# Serial_Load_Cell_converter.net
KiCad netlist of a schematic drawn in EAGLE
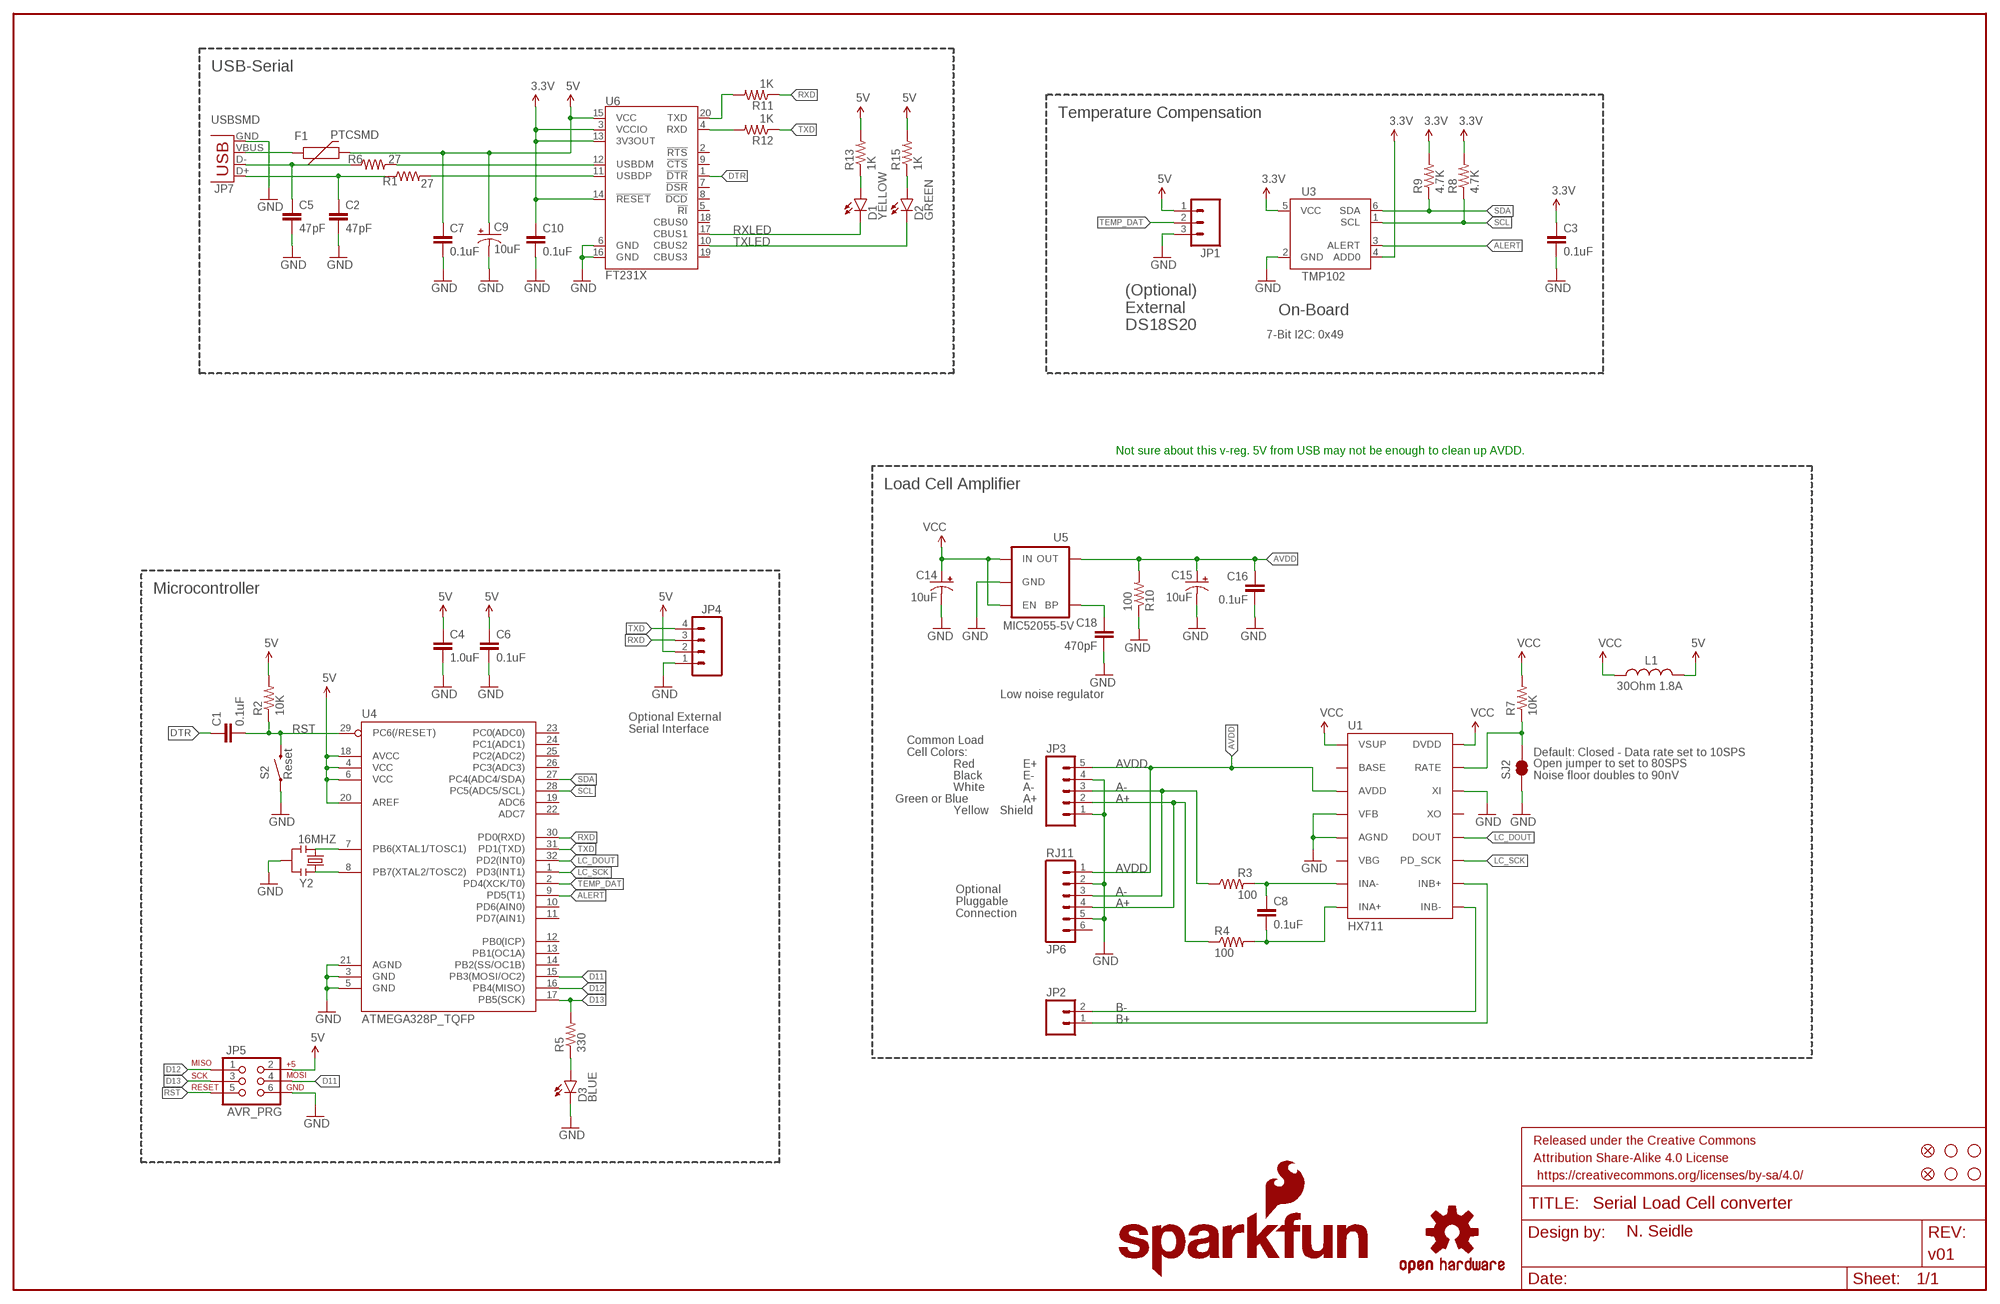
[diagram p0: schematic, sheet 1]

(export (version "E")
  (design (tool "Eeschema 10.0.6"))
  (components
    (comp (ref "C1")
      (value "0.1uF")
      (footprint "eagle-import:0603-CAP")
      (libsource (lib "eagle-import") (part "0.1UF-25V(+80/-20%)(0603)"))
    )
    (comp (ref "C2")
      (value "47pF")
      (footprint "eagle-import:0603-CAP")
      (libsource (lib "eagle-import") (part "47PF-50V-5%(0603)"))
    )
    (comp (ref "C3")
      (value "0.1uF")
      (footprint "eagle-import:0603-CAP")
      (libsource (lib "eagle-import") (part "0.1UF-25V-5%(0603)"))
    )
    (comp (ref "C4")
      (value "1.0uF")
      (footprint "eagle-import:0603-CAP")
      (libsource (lib "eagle-import") (part "1.0UF-16V-10%(0603)"))
    )
    (comp (ref "C5")
      (value "47pF")
      (footprint "eagle-import:0603-CAP")
      (libsource (lib "eagle-import") (part "47PF-50V-5%(0603)"))
    )
    (comp (ref "C6")
      (value "0.1uF")
      (footprint "eagle-import:0603-CAP")
      (libsource (lib "eagle-import") (part "0.1UF-25V(+80/-20%)(0603)"))
    )
    (comp (ref "C7")
      (value "0.1uF")
      (footprint "eagle-import:0603-CAP")
      (libsource (lib "eagle-import") (part "0.1UF-25V(+80/-20%)(0603)"))
    )
    (comp (ref "C8")
      (value "0.1uF")
      (footprint "eagle-import:0603-CAP")
      (libsource (lib "eagle-import") (part "0.1UF-25V-5%(0603)"))
    )
    (comp (ref "C9")
      (value "10uF")
      (footprint "eagle-import:EIA3216")
      (libsource (lib "eagle-import") (part "10UF-16V-10%(TANT)"))
    )
    (comp (ref "C10")
      (value "0.1uF")
      (footprint "eagle-import:0603-CAP")
      (libsource (lib "eagle-import") (part "0.1UF-25V(+80/-20%)(0603)"))
    )
    (comp (ref "C14")
      (value "10uF")
      (footprint "eagle-import:EIA3216")
      (libsource (lib "eagle-import") (part "10UF-16V-10%(TANT)"))
    )
    (comp (ref "C15")
      (value "10uF")
      (footprint "eagle-import:EIA3216")
      (libsource (lib "eagle-import") (part "10UF-16V-10%(TANT)"))
    )
    (comp (ref "C16")
      (value "0.1uF")
      (footprint "eagle-import:0603-CAP")
      (libsource (lib "eagle-import") (part "0.1UF-25V-5%(0603)"))
    )
    (comp (ref "C18")
      (value "470pF")
      (footprint "eagle-import:0603-CAP")
      (libsource (lib "eagle-import") (part "470PF-50V-5%(0603)SMD"))
    )
    (comp (ref "D1")
      (value "YELLOW")
      (footprint "eagle-import:LED-1206")
      (libsource (lib "eagle-import") (part "LED-YELLOWLARGE"))
    )
    (comp (ref "D2")
      (value "GREEN")
      (footprint "eagle-import:LED-1206")
      (libsource (lib "eagle-import") (part "LED-GREENLARGE"))
    )
    (comp (ref "D3")
      (value "BLUE")
      (footprint "eagle-import:LED-1206")
      (libsource (lib "eagle-import") (part "LED-BLUE1206"))
    )
    (comp (ref "F1")
      (value "PTCSMD")
      (footprint "eagle-import:PTC-1206")
      (libsource (lib "eagle-import") (part "PTCSMD"))
    )
    (comp (ref "FID1")
      (value "FIDUCIAL1X2")
      (footprint "eagle-import:FIDUCIAL-1X2")
      (libsource (lib "eagle-import") (part "FIDUCIAL1X2"))
    )
    (comp (ref "FID2")
      (value "FIDUCIAL1X2")
      (footprint "eagle-import:FIDUCIAL-1X2")
      (libsource (lib "eagle-import") (part "FIDUCIAL1X2"))
    )
    (comp (ref "FRAME1")
      (value "FRAME-LEDGER")
      (footprint "eagle-import:CREATIVE_COMMONS")
      (fields (field (name "DESIGNER") "N. Seidle") (field (name "VERSION") "v01"))
      (libsource (lib "eagle-import") (part "FRAME-LEDGER"))
    )
    (comp (ref "JP1")
      (value "M03PTH")
      (footprint "eagle-import:1X03")
      (libsource (lib "eagle-import") (part "M03PTH"))
    )
    (comp (ref "JP2")
      (value "M02PTH")
      (footprint "eagle-import:1X02")
      (libsource (lib "eagle-import") (part "M02PTH"))
    )
    (comp (ref "JP3")
      (value "M05PTH")
      (footprint "eagle-import:1X05")
      (libsource (lib "eagle-import") (part "M05PTH"))
    )
    (comp (ref "JP4")
      (value "M04PTH")
      (footprint "eagle-import:1X04")
      (libsource (lib "eagle-import") (part "M04PTH"))
    )
    (comp (ref "JP5")
      (value "AVR_PRG")
      (footprint "eagle-import:2X3")
      (libsource (lib "eagle-import") (part "AVR_SPI_PRG_6PTH"))
    )
    (comp (ref "JP6")
      (value "RJ11")
      (footprint "eagle-import:RJ11-6")
      (libsource (lib "eagle-import") (part "RJ11-6PTH"))
    )
    (comp (ref "JP7")
      (value "USBSMD")
      (footprint "eagle-import:USB-MINIB")
      (libsource (lib "eagle-import") (part "USBSMD"))
    )
    (comp (ref "L1")
      (value "30Ohm 1.8A")
      (footprint "eagle-import:0603")
      (libsource (lib "eagle-import") (part "INDUCTOR30OHM,1.8A"))
    )
    (comp (ref "LOGO1")
      (value "SFE_LOGO_NAME_FLAME.1_INCH")
      (footprint "eagle-import:SFE_LOGO_NAME_FLAME_.1")
      (libsource (lib "eagle-import") (part "SFE_LOGO_NAME_FLAME.1_INCH"))
    )
    (comp (ref "LOGO2")
      (value "OSHW-LOGOS")
      (footprint "eagle-import:OSHW-LOGO-S")
      (libsource (lib "eagle-import") (part "OSHW-LOGOS"))
    )
    (comp (ref "LOGO4")
      (value "SFE_LOGO_NAME_FLAME.1_INCH")
      (footprint "eagle-import:SFE_LOGO_NAME_FLAME_.1")
      (libsource (lib "eagle-import") (part "SFE_LOGO_NAME_FLAME.1_INCH"))
    )
    (comp (ref "R1")
      (value "27")
      (footprint "eagle-import:0603")
      (libsource (lib "eagle-import") (part "27OHM1/10W1%(0603)"))
    )
    (comp (ref "R2")
      (value "10K")
      (footprint "eagle-import:0603-RES")
      (libsource (lib "eagle-import") (part "10KOHM-1/10W-1%(0603)0603"))
    )
    (comp (ref "R3")
      (value "100")
      (footprint "eagle-import:0603-RES")
      (libsource (lib "eagle-import") (part "100OHM-1/10W-1%(0603)"))
    )
    (comp (ref "R4")
      (value "100")
      (footprint "eagle-import:0603-RES")
      (libsource (lib "eagle-import") (part "100OHM-1/10W-1%(0603)"))
    )
    (comp (ref "R5")
      (value "330")
      (footprint "eagle-import:0603-RES")
      (libsource (lib "eagle-import") (part "330OHM1/10W1%(0603)"))
    )
    (comp (ref "R6")
      (value "27")
      (footprint "eagle-import:0603")
      (libsource (lib "eagle-import") (part "27OHM1/10W1%(0603)"))
    )
    (comp (ref "R7")
      (value "10K")
      (footprint "eagle-import:0603-RES")
      (libsource (lib "eagle-import") (part "10KOHM-1/10W-1%(0603)0603"))
    )
    (comp (ref "R8")
      (value "4.7K")
      (footprint "eagle-import:0603-RES")
      (libsource (lib "eagle-import") (part "4.7KOHM-1/10W-1%(0603)"))
    )
    (comp (ref "R9")
      (value "4.7K")
      (footprint "eagle-import:0603-RES")
      (libsource (lib "eagle-import") (part "4.7KOHM-1/10W-1%(0603)"))
    )
    (comp (ref "R10")
      (value "100")
      (footprint "eagle-import:0603-RES")
      (libsource (lib "eagle-import") (part "100OHM-1/10W-1%(0603)"))
    )
    (comp (ref "R11")
      (value "1K")
      (footprint "eagle-import:0603-RES")
      (libsource (lib "eagle-import") (part "1KOHM-1/10W-1%(0603)"))
    )
    (comp (ref "R12")
      (value "1K")
      (footprint "eagle-import:0603-RES")
      (libsource (lib "eagle-import") (part "1KOHM-1/10W-1%(0603)"))
    )
    (comp (ref "R13")
      (value "1K")
      (footprint "eagle-import:0603-RES")
      (libsource (lib "eagle-import") (part "1KOHM-1/10W-1%(0603)"))
    )
    (comp (ref "R15")
      (value "1K")
      (footprint "eagle-import:0603-RES")
      (libsource (lib "eagle-import") (part "1KOHM-1/10W-1%(0603)"))
    )
    (comp (ref "S2")
      (value "Reset")
      (footprint "eagle-import:TACTILE-SWITCH-SMD")
      (libsource (lib "eagle-import") (part "SWITCH-MOMENTARY-2SMD"))
    )
    (comp (ref "SJ2")
      (value "JUMPER-PAD-2-NC_BY_TRACE")
      (footprint "eagle-import:PAD-JUMPER-2-NC_BY_TRACE_YES_SILK")
      (libsource (lib "eagle-import") (part "JUMPER-PAD-2-NC_BY_TRACE"))
    )
    (comp (ref "STANDOFF1")
      (value "STAND-OFF")
      (footprint "eagle-import:STAND-OFF")
      (libsource (lib "eagle-import") (part "STAND-OFF"))
    )
    (comp (ref "STANDOFF2")
      (value "STAND-OFF")
      (footprint "eagle-import:STAND-OFF")
      (libsource (lib "eagle-import") (part "STAND-OFF"))
    )
    (comp (ref "STANDOFF3")
      (value "STAND-OFF")
      (footprint "eagle-import:STAND-OFF")
      (libsource (lib "eagle-import") (part "STAND-OFF"))
    )
    (comp (ref "STANDOFF4")
      (value "STAND-OFF")
      (footprint "eagle-import:STAND-OFF")
      (libsource (lib "eagle-import") (part "STAND-OFF"))
    )
    (comp (ref "U1")
      (value "HX711")
      (footprint "eagle-import:SO16")
      (libsource (lib "eagle-import") (part "HX711HX711"))
    )
    (comp (ref "U3")
      (value "TMP102")
      (footprint "eagle-import:SOT563")
      (libsource (lib "eagle-import") (part "TMP102"))
    )
    (comp (ref "U4")
      (value "ATMEGA328P_TQFP")
      (footprint "eagle-import:TQFP32-08")
      (libsource (lib "eagle-import") (part "ATMEGA328P_TQFP"))
    )
    (comp (ref "U5")
      (value "MIC52055-5V")
      (footprint "eagle-import:SOT23-5")
      (libsource (lib "eagle-import") (part "MIC52055V"))
    )
    (comp (ref "U6")
      (value "FT231X")
      (footprint "eagle-import:SSOP20_L")
      (libsource (lib "eagle-import") (part "FT231XS"))
    )
    (comp (ref "Y2")
      (value "16MHZ")
      (footprint "eagle-import:RESONATOR-SMD")
      (libsource (lib "eagle-import") (part "RESONATOR16MHZ"))
    )
  )
  (nets
    (net (code "1") (name "/A+") (class "Default")
      (node (ref "JP3") (pin "2") (pinfunction "2_2") (pintype "passive"))
      (node (ref "JP6") (pin "4") (pinfunction "4_4") (pintype "passive"))
      (node (ref "R4") (pin "1") (pinfunction "1_1") (pintype "passive"))
    )
    (net (code "2") (name "/A-") (class "Default")
      (node (ref "JP3") (pin "3") (pinfunction "3_3") (pintype "passive"))
      (node (ref "JP6") (pin "3") (pinfunction "3_3") (pintype "passive"))
      (node (ref "R3") (pin "1") (pinfunction "1_1") (pintype "passive"))
    )
    (net (code "3") (name "/B+") (class "Default")
      (node (ref "JP2") (pin "1") (pinfunction "1_1") (pintype "passive"))
      (node (ref "U1") (pin "10") (pinfunction "INB+_10") (pintype "bidirectional"))
    )
    (net (code "4") (name "/B-") (class "Default")
      (node (ref "JP2") (pin "2") (pinfunction "2_2") (pintype "passive"))
      (node (ref "U1") (pin "9") (pinfunction "INB-_9") (pintype "bidirectional"))
    )
    (net (code "5") (name "/RXLED") (class "Default")
      (node (ref "D1") (pin "C") (pinfunction "C_C") (pintype "passive"))
      (node (ref "U6") (pin "17") (pinfunction "CBUS1_17") (pintype "bidirectional"))
    )
    (net (code "6") (name "/TXLED") (class "Default")
      (node (ref "D2") (pin "C") (pinfunction "C_C") (pintype "passive"))
      (node (ref "U6") (pin "10") (pinfunction "CBUS2_10") (pintype "bidirectional"))
    )
    (net (code "7") (name "3.3V") (class "Default")
      (node (ref "C10") (pin "1") (pinfunction "1_1") (pintype "passive"))
      (node (ref "C3") (pin "1") (pinfunction "1_1") (pintype "passive"))
      (node (ref "R8") (pin "2") (pinfunction "2_2") (pintype "passive"))
      (node (ref "R9") (pin "2") (pinfunction "2_2") (pintype "passive"))
      (node (ref "U3") (pin "4") (pinfunction "ADD0_4") (pintype "bidirectional"))
      (node (ref "U3") (pin "5") (pinfunction "VCC_5") (pintype "bidirectional"))
      (node (ref "U6") (pin "13") (pinfunction "3V3OUT_13") (pintype "bidirectional"))
      (node (ref "U6") (pin "14") (pinfunction "~{RESET}_14") (pintype "bidirectional"))
      (node (ref "U6") (pin "3") (pinfunction "VCCIO_3") (pintype "bidirectional"))
    )
    (net (code "8") (name "5V") (class "Default")
      (node (ref "C4") (pin "1") (pinfunction "1_1") (pintype "passive"))
      (node (ref "C6") (pin "1") (pinfunction "1_1") (pintype "passive"))
      (node (ref "C7") (pin "1") (pinfunction "1_1") (pintype "passive"))
      (node (ref "C9") (pin "A") (pinfunction "+_A") (pintype "passive"))
      (node (ref "F1") (pin "2") (pinfunction "2_2") (pintype "bidirectional"))
      (node (ref "JP1") (pin "1") (pinfunction "1_1") (pintype "passive"))
      (node (ref "JP4") (pin "2") (pinfunction "2_2") (pintype "passive"))
      (node (ref "JP5") (pin "2") (pinfunction "2_2") (pintype "passive"))
      (node (ref "L1") (pin "2") (pinfunction "2_2") (pintype "passive"))
      (node (ref "R13") (pin "2") (pinfunction "2_2") (pintype "passive"))
      (node (ref "R15") (pin "2") (pinfunction "2_2") (pintype "passive"))
      (node (ref "R2") (pin "2") (pinfunction "2_2") (pintype "passive"))
      (node (ref "U4") (pin "18") (pinfunction "AVCC_18") (pintype "bidirectional"))
      (node (ref "U4") (pin "20") (pinfunction "AREF_20") (pintype "bidirectional"))
      (node (ref "U4") (pin "4") (pinfunction "VCC_4") (pintype "bidirectional"))
      (node (ref "U4") (pin "6") (pinfunction "VCC_6") (pintype "bidirectional"))
      (node (ref "U6") (pin "15") (pinfunction "VCC_15") (pintype "bidirectional"))
    )
    (net (code "9") (name "ALERT") (class "Default")
      (node (ref "U3") (pin "3") (pinfunction "ALERT_3") (pintype "bidirectional"))
      (node (ref "U4") (pin "9") (pinfunction "PD5(T1)_9") (pintype "bidirectional"))
    )
    (net (code "10") (name "AVDD") (class "Default")
      (node (ref "C15") (pin "A") (pinfunction "+_A") (pintype "passive"))
      (node (ref "C16") (pin "1") (pinfunction "1_1") (pintype "passive"))
      (node (ref "JP3") (pin "5") (pinfunction "5_5") (pintype "passive"))
      (node (ref "JP6") (pin "1") (pinfunction "1_1") (pintype "passive"))
      (node (ref "R10") (pin "2") (pinfunction "2_2") (pintype "passive"))
      (node (ref "U1") (pin "3") (pinfunction "AVDD_3") (pintype "bidirectional"))
      (node (ref "U5") (pin "5") (pinfunction "OUT_5") (pintype "passive"))
    )
    (net (code "11") (name "D11") (class "Default")
      (node (ref "JP5") (pin "4") (pinfunction "4_4") (pintype "passive"))
      (node (ref "U4") (pin "15") (pinfunction "PB3(MOSI/OC2)_15") (pintype "bidirectional"))
    )
    (net (code "12") (name "D12") (class "Default")
      (node (ref "JP5") (pin "1") (pinfunction "1_1") (pintype "passive"))
      (node (ref "U4") (pin "16") (pinfunction "PB4(MISO)_16") (pintype "bidirectional"))
    )
    (net (code "13") (name "D13") (class "Default")
      (node (ref "JP5") (pin "3") (pinfunction "3_3") (pintype "passive"))
      (node (ref "R5") (pin "2") (pinfunction "2_2") (pintype "passive"))
      (node (ref "U4") (pin "17") (pinfunction "PB5(SCK)_17") (pintype "bidirectional"))
    )
    (net (code "14") (name "DTR") (class "Default")
      (node (ref "C1") (pin "1") (pinfunction "1_1") (pintype "passive"))
      (node (ref "U6") (pin "1") (pinfunction "~{DTR}_1") (pintype "bidirectional"))
    )
    (net (code "15") (name "GND") (class "Default")
      (node (ref "C10") (pin "2") (pinfunction "2_2") (pintype "passive"))
      (node (ref "C14") (pin "C") (pinfunction "-_C") (pintype "passive"))
      (node (ref "C15") (pin "C") (pinfunction "-_C") (pintype "passive"))
      (node (ref "C16") (pin "2") (pinfunction "2_2") (pintype "passive"))
      (node (ref "C18") (pin "2") (pinfunction "2_2") (pintype "passive"))
      (node (ref "C2") (pin "2") (pinfunction "2_2") (pintype "passive"))
      (node (ref "C3") (pin "2") (pinfunction "2_2") (pintype "passive"))
      (node (ref "C4") (pin "2") (pinfunction "2_2") (pintype "passive"))
      (node (ref "C5") (pin "2") (pinfunction "2_2") (pintype "passive"))
      (node (ref "C6") (pin "2") (pinfunction "2_2") (pintype "passive"))
      (node (ref "C7") (pin "2") (pinfunction "2_2") (pintype "passive"))
      (node (ref "C9") (pin "C") (pinfunction "-_C") (pintype "passive"))
      (node (ref "D3") (pin "C") (pinfunction "C_C") (pintype "passive"))
      (node (ref "JP1") (pin "3") (pinfunction "3_3") (pintype "passive"))
      (node (ref "JP3") (pin "1") (pinfunction "1_1") (pintype "passive"))
      (node (ref "JP3") (pin "4") (pinfunction "4_4") (pintype "passive"))
      (node (ref "JP4") (pin "1") (pinfunction "1_1") (pintype "passive"))
      (node (ref "JP5") (pin "6") (pinfunction "6_6") (pintype "passive"))
      (node (ref "JP6") (pin "2") (pinfunction "2_2") (pintype "passive"))
      (node (ref "JP6") (pin "5") (pinfunction "5_5") (pintype "passive"))
      (node (ref "JP7") (pin "GND") (pinfunction "GND_GND") (pintype "bidirectional"))
      (node (ref "R10") (pin "1") (pinfunction "1_1") (pintype "passive"))
      (node (ref "S2") (pin "1") (pinfunction "1_1") (pintype "passive"))
      (node (ref "SJ2") (pin "1") (pinfunction "1_1") (pintype "passive"))
      (node (ref "U1") (pin "14") (pinfunction "XI_14") (pintype "bidirectional"))
      (node (ref "U1") (pin "4") (pinfunction "VFB_4") (pintype "bidirectional"))
      (node (ref "U1") (pin "5") (pinfunction "AGND_5") (pintype "bidirectional"))
      (node (ref "U3") (pin "2") (pinfunction "GND_2") (pintype "bidirectional"))
      (node (ref "U4") (pin "21") (pinfunction "AGND_21") (pintype "bidirectional"))
      (node (ref "U4") (pin "3") (pinfunction "GND_3") (pintype "bidirectional"))
      (node (ref "U4") (pin "5") (pinfunction "GND_5") (pintype "bidirectional"))
      (node (ref "U5") (pin "2") (pinfunction "GND_2") (pintype "input"))
      (node (ref "U6") (pin "16") (pinfunction "GND_16") (pintype "bidirectional"))
      (node (ref "U6") (pin "6") (pinfunction "GND_6") (pintype "bidirectional"))
      (node (ref "Y2") (pin "2") (pinfunction "2_2") (pintype "passive"))
    )
    (net (code "16") (name "LC_DOUT") (class "Default")
      (node (ref "U1") (pin "12") (pinfunction "DOUT_12") (pintype "bidirectional"))
      (node (ref "U4") (pin "32") (pinfunction "PD2(INT0)_32") (pintype "bidirectional"))
    )
    (net (code "17") (name "LC_SCK") (class "Default")
      (node (ref "U1") (pin "11") (pinfunction "PD_SCK_11") (pintype "bidirectional"))
      (node (ref "U4") (pin "1") (pinfunction "PD3(INT1)_1") (pintype "bidirectional"))
    )
    (net (code "18") (name "Net-(C2-Pad1)") (class "Default")
      (node (ref "C2") (pin "1") (pinfunction "1_1") (pintype "passive"))
      (node (ref "JP7") (pin "D+") (pinfunction "D+_D+") (pintype "bidirectional"))
      (node (ref "R1") (pin "1") (pinfunction "1_1") (pintype "passive"))
    )
    (net (code "19") (name "Net-(C5-Pad1)") (class "Default")
      (node (ref "C5") (pin "1") (pinfunction "1_1") (pintype "passive"))
      (node (ref "JP7") (pin "D-") (pinfunction "D-_D-") (pintype "bidirectional"))
      (node (ref "R6") (pin "1") (pinfunction "1_1") (pintype "passive"))
    )
    (net (code "20") (name "Net-(D1-PadA)") (class "Default")
      (node (ref "D1") (pin "A") (pinfunction "A_A") (pintype "passive"))
      (node (ref "R13") (pin "1") (pinfunction "1_1") (pintype "passive"))
    )
    (net (code "21") (name "Net-(D2-PadA)") (class "Default")
      (node (ref "D2") (pin "A") (pinfunction "A_A") (pintype "passive"))
      (node (ref "R15") (pin "1") (pinfunction "1_1") (pintype "passive"))
    )
    (net (code "22") (name "Net-(D3-PadA)") (class "Default")
      (node (ref "D3") (pin "A") (pinfunction "A_A") (pintype "passive"))
      (node (ref "R5") (pin "1") (pinfunction "1_1") (pintype "passive"))
    )
    (net (code "23") (name "Net-(F1-Pad1)") (class "Default")
      (node (ref "F1") (pin "1") (pinfunction "1_1") (pintype "bidirectional"))
      (node (ref "JP7") (pin "VBUS") (pinfunction "VBUS_VBUS") (pintype "bidirectional"))
    )
    (net (code "24") (name "Net-(U1-INA+)") (class "Default")
      (node (ref "C8") (pin "2") (pinfunction "2_2") (pintype "passive"))
      (node (ref "R4") (pin "2") (pinfunction "2_2") (pintype "passive"))
      (node (ref "U1") (pin "8") (pinfunction "INA+_8") (pintype "bidirectional"))
    )
    (net (code "25") (name "Net-(U1-INA-)") (class "Default")
      (node (ref "C8") (pin "1") (pinfunction "1_1") (pintype "passive"))
      (node (ref "R3") (pin "2") (pinfunction "2_2") (pintype "passive"))
      (node (ref "U1") (pin "7") (pinfunction "INA-_7") (pintype "bidirectional"))
    )
    (net (code "26") (name "Net-(U1-RATE)") (class "Default")
      (node (ref "R7") (pin "1") (pinfunction "1_1") (pintype "passive"))
      (node (ref "SJ2") (pin "2") (pinfunction "2_2") (pintype "passive"))
      (node (ref "U1") (pin "15") (pinfunction "RATE_15") (pintype "bidirectional"))
    )
    (net (code "27") (name "Net-(U4-PB6(XTAL1{slash}TOSC1))") (class "Default")
      (node (ref "U4") (pin "7") (pinfunction "PB6(XTAL1/TOSC1)_7") (pintype "bidirectional"))
      (node (ref "Y2") (pin "1") (pinfunction "1_1") (pintype "passive"))
    )
    (net (code "28") (name "Net-(U4-PB7(XTAL2{slash}TOSC2))") (class "Default")
      (node (ref "U4") (pin "8") (pinfunction "PB7(XTAL2/TOSC2)_8") (pintype "bidirectional"))
      (node (ref "Y2") (pin "3") (pinfunction "3_3") (pintype "passive"))
    )
    (net (code "29") (name "Net-(U5-BP)") (class "Default")
      (node (ref "C18") (pin "1") (pinfunction "1_1") (pintype "passive"))
      (node (ref "U5") (pin "4") (pinfunction "BP_4") (pintype "input"))
    )
    (net (code "30") (name "Net-(U6-RXD)") (class "Default")
      (node (ref "R12") (pin "2") (pinfunction "2_2") (pintype "passive"))
      (node (ref "U6") (pin "4") (pinfunction "RXD_4") (pintype "bidirectional"))
    )
    (net (code "31") (name "Net-(U6-TXD)") (class "Default")
      (node (ref "R11") (pin "2") (pinfunction "2_2") (pintype "passive"))
      (node (ref "U6") (pin "20") (pinfunction "TXD_20") (pintype "bidirectional"))
    )
    (net (code "32") (name "Net-(U6-USBDM)") (class "Default")
      (node (ref "R6") (pin "2") (pinfunction "2_2") (pintype "passive"))
      (node (ref "U6") (pin "12") (pinfunction "USBDM_12") (pintype "bidirectional"))
    )
    (net (code "33") (name "Net-(U6-USBDP)") (class "Default")
      (node (ref "R1") (pin "2") (pinfunction "2_2") (pintype "passive"))
      (node (ref "U6") (pin "11") (pinfunction "USBDP_11") (pintype "bidirectional"))
    )
    (net (code "34") (name "RST") (class "Default")
      (node (ref "C1") (pin "2") (pinfunction "2_2") (pintype "passive"))
      (node (ref "JP5") (pin "5") (pinfunction "5_5") (pintype "passive"))
      (node (ref "R2") (pin "1") (pinfunction "1_1") (pintype "passive"))
      (node (ref "S2") (pin "3") (pinfunction "2_3") (pintype "passive"))
      (node (ref "U4") (pin "29") (pinfunction "PC6(/RESET)_29") (pintype "bidirectional"))
    )
    (net (code "35") (name "RXD") (class "Default")
      (node (ref "JP4") (pin "3") (pinfunction "3_3") (pintype "passive"))
      (node (ref "R11") (pin "1") (pinfunction "1_1") (pintype "passive"))
      (node (ref "U4") (pin "30") (pinfunction "PD0(RXD)_30") (pintype "bidirectional"))
    )
    (net (code "36") (name "SCL") (class "Default")
      (node (ref "R8") (pin "1") (pinfunction "1_1") (pintype "passive"))
      (node (ref "U3") (pin "1") (pinfunction "SCL_1") (pintype "bidirectional"))
      (node (ref "U4") (pin "28") (pinfunction "PC5(ADC5/SCL)_28") (pintype "bidirectional"))
    )
    (net (code "37") (name "SDA") (class "Default")
      (node (ref "R9") (pin "1") (pinfunction "1_1") (pintype "passive"))
      (node (ref "U3") (pin "6") (pinfunction "SDA_6") (pintype "bidirectional"))
      (node (ref "U4") (pin "27") (pinfunction "PC4(ADC4/SDA)_27") (pintype "bidirectional"))
    )
    (net (code "38") (name "TEMP_DAT") (class "Default")
      (node (ref "JP1") (pin "2") (pinfunction "2_2") (pintype "passive"))
      (node (ref "U4") (pin "2") (pinfunction "PD4(XCK/T0)_2") (pintype "bidirectional"))
    )
    (net (code "39") (name "TXD") (class "Default")
      (node (ref "JP4") (pin "4") (pinfunction "4_4") (pintype "passive"))
      (node (ref "R12") (pin "1") (pinfunction "1_1") (pintype "passive"))
      (node (ref "U4") (pin "31") (pinfunction "PD1(TXD)_31") (pintype "bidirectional"))
    )
    (net (code "40") (name "VCC") (class "Default")
      (node (ref "C14") (pin "A") (pinfunction "+_A") (pintype "passive"))
      (node (ref "L1") (pin "1") (pinfunction "1_1") (pintype "passive"))
      (node (ref "R7") (pin "2") (pinfunction "2_2") (pintype "passive"))
      (node (ref "U1") (pin "1") (pinfunction "VSUP_1") (pintype "bidirectional"))
      (node (ref "U1") (pin "16") (pinfunction "DVDD_16") (pintype "bidirectional"))
      (node (ref "U5") (pin "1") (pinfunction "IN_1") (pintype "input"))
      (node (ref "U5") (pin "3") (pinfunction "EN_3") (pintype "input"))
    )
    (net (code "41") (name "unconnected-(JP6-Pad6)") (class "Default")
      (node (ref "JP6") (pin "6") (pinfunction "6_6") (pintype "passive"))
    )
    (net (code "42") (name "unconnected-(U1-BASE-Pad2)") (class "Default")
      (node (ref "U1") (pin "2") (pinfunction "BASE_2") (pintype "bidirectional"))
    )
    (net (code "43") (name "unconnected-(U1-VBG-Pad6)") (class "Default")
      (node (ref "U1") (pin "6") (pinfunction "VBG_6") (pintype "bidirectional"))
    )
    (net (code "44") (name "unconnected-(U1-XO-Pad13)") (class "Default")
      (node (ref "U1") (pin "13") (pinfunction "XO_13") (pintype "bidirectional"))
    )
    (net (code "45") (name "unconnected-(U4-ADC6-Pad19)") (class "Default")
      (node (ref "U4") (pin "19") (pinfunction "ADC6_19") (pintype "bidirectional"))
    )
    (net (code "46") (name "unconnected-(U4-ADC7-Pad22)") (class "Default")
      (node (ref "U4") (pin "22") (pinfunction "ADC7_22") (pintype "bidirectional"))
    )
    (net (code "47") (name "unconnected-(U4-PB0(ICP)-Pad12)") (class "Default")
      (node (ref "U4") (pin "12") (pinfunction "PB0(ICP)_12") (pintype "bidirectional"))
    )
    (net (code "48") (name "unconnected-(U4-PB1(OC1A)-Pad13)") (class "Default")
      (node (ref "U4") (pin "13") (pinfunction "PB1(OC1A)_13") (pintype "bidirectional"))
    )
    (net (code "49") (name "unconnected-(U4-PB2(SS{slash}OC1B)-Pad14)") (class "Default")
      (node (ref "U4") (pin "14") (pinfunction "PB2(SS/OC1B)_14") (pintype "bidirectional"))
    )
    (net (code "50") (name "unconnected-(U4-PC0(ADC0)-Pad23)") (class "Default")
      (node (ref "U4") (pin "23") (pinfunction "PC0(ADC0)_23") (pintype "bidirectional"))
    )
    (net (code "51") (name "unconnected-(U4-PC1(ADC1)-Pad24)") (class "Default")
      (node (ref "U4") (pin "24") (pinfunction "PC1(ADC1)_24") (pintype "bidirectional"))
    )
    (net (code "52") (name "unconnected-(U4-PC2(ADC2)-Pad25)") (class "Default")
      (node (ref "U4") (pin "25") (pinfunction "PC2(ADC2)_25") (pintype "bidirectional"))
    )
    (net (code "53") (name "unconnected-(U4-PC3(ADC3)-Pad26)") (class "Default")
      (node (ref "U4") (pin "26") (pinfunction "PC3(ADC3)_26") (pintype "bidirectional"))
    )
    (net (code "54") (name "unconnected-(U4-PD6(AIN0)-Pad10)") (class "Default")
      (node (ref "U4") (pin "10") (pinfunction "PD6(AIN0)_10") (pintype "bidirectional"))
    )
    (net (code "55") (name "unconnected-(U4-PD7(AIN1)-Pad11)") (class "Default")
      (node (ref "U4") (pin "11") (pinfunction "PD7(AIN1)_11") (pintype "bidirectional"))
    )
    (net (code "56") (name "unconnected-(U6-CBUS0-Pad18)") (class "Default")
      (node (ref "U6") (pin "18") (pinfunction "CBUS0_18") (pintype "bidirectional"))
    )
    (net (code "57") (name "unconnected-(U6-CBUS3-Pad19)") (class "Default")
      (node (ref "U6") (pin "19") (pinfunction "CBUS3_19") (pintype "bidirectional"))
    )
    (net (code "58") (name "unconnected-(U6-~{CTS}-Pad9)") (class "Default")
      (node (ref "U6") (pin "9") (pinfunction "~{CTS}_9") (pintype "bidirectional"))
    )
    (net (code "59") (name "unconnected-(U6-~{DCD}-Pad8)") (class "Default")
      (node (ref "U6") (pin "8") (pinfunction "~{DCD}_8") (pintype "bidirectional"))
    )
    (net (code "60") (name "unconnected-(U6-~{DSR}-Pad7)") (class "Default")
      (node (ref "U6") (pin "7") (pinfunction "~{DSR}_7") (pintype "bidirectional"))
    )
    (net (code "61") (name "unconnected-(U6-~{RI}-Pad5)") (class "Default")
      (node (ref "U6") (pin "5") (pinfunction "~{RI}_5") (pintype "bidirectional"))
    )
    (net (code "62") (name "unconnected-(U6-~{RTS}-Pad2)") (class "Default")
      (node (ref "U6") (pin "2") (pinfunction "~{RTS}_2") (pintype "bidirectional"))
    )
  )
)
